# Regulators.net
KiCad netlist of a schematic drawn in Altium Designer
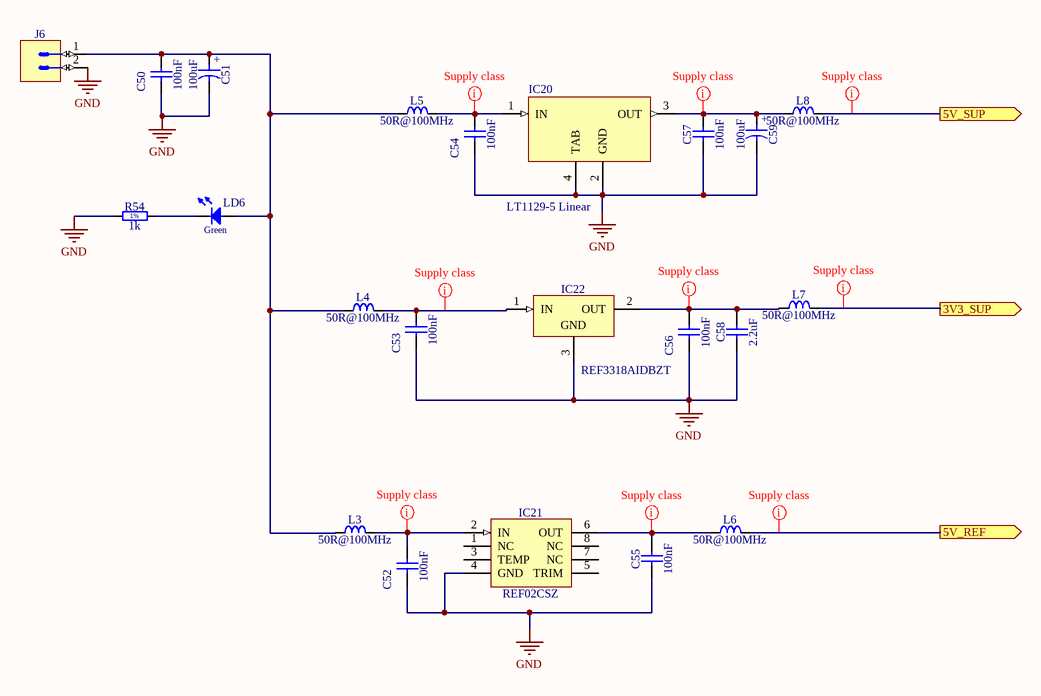
[diagram p0: Regulators.SchDoc]

(export (version "E")
  (design (tool "Eeschema 10.0.6"))
  (components
    (comp (ref "C50")
      (value "100nF")
      (footprint "CAPC2012X135N")
      (description "Non-polarised capacitor")
      (fields
        (field (name "PART NUMBER") "CC0805_100NF_50V_10%_X7R")
        (field (name "VOLTAGE") "50V")
        (field (name "AUTHOR") "CERN DEM JLC")
      )
      (libsource (lib "Capacitors") (part "Capacitor - non polarized"))
    )
    (comp (ref "C51")
      (value "100uF")
      (footprint "CAPAE660X540N")
      (description "Polarised capacitor")
      (fields
        (field (name "PART NUMBER") "CAE660-540_100UF_16V_20%")
        (field (name "VOLTAGE") "16V")
        (field (name "AUTHOR") "CERN DEM JLC")
      )
      (libsource (lib "Capacitors") (part "Capacitor - polarized"))
    )
    (comp (ref "C52")
      (value "100nF")
      (footprint "CAPC2012X135N")
      (description "Non-polarised capacitor")
      (fields
        (field (name "PART NUMBER") "CC0805_100NF_50V_10%_X7R")
        (field (name "VOLTAGE") "50V")
        (field (name "AUTHOR") "CERN DEM JLC")
      )
      (libsource (lib "Capacitors") (part "Capacitor - non polarized"))
    )
    (comp (ref "C53")
      (value "100nF")
      (footprint "CAPC2012X135N")
      (description "Non-polarised capacitor")
      (fields
        (field (name "PART NUMBER") "CC0805_100NF_50V_10%_X7R")
        (field (name "VOLTAGE") "50V")
        (field (name "AUTHOR") "CERN DEM JLC")
      )
      (libsource (lib "Capacitors") (part "Capacitor - non polarized"))
    )
    (comp (ref "C54")
      (value "100nF")
      (footprint "CAPC2012X135N")
      (description "Non-polarised capacitor")
      (fields
        (field (name "PART NUMBER") "CC0805_100NF_50V_10%_X7R")
        (field (name "VOLTAGE") "50V")
        (field (name "AUTHOR") "CERN DEM JLC")
      )
      (libsource (lib "Capacitors") (part "Capacitor - non polarized"))
    )
    (comp (ref "C55")
      (value "100nF")
      (footprint "CAPC2012X135N")
      (description "Non-polarised capacitor")
      (fields
        (field (name "PART NUMBER") "CC0805_100NF_50V_10%_X7R")
        (field (name "VOLTAGE") "50V")
        (field (name "AUTHOR") "CERN DEM JLC")
      )
      (libsource (lib "Capacitors") (part "Capacitor - non polarized"))
    )
    (comp (ref "C56")
      (value "100nF")
      (footprint "CAPC2012X135N")
      (description "Non-polarised capacitor")
      (fields
        (field (name "PART NUMBER") "CC0805_100NF_50V_10%_X7R")
        (field (name "VOLTAGE") "50V")
        (field (name "AUTHOR") "CERN DEM JLC")
      )
      (libsource (lib "Capacitors") (part "Capacitor - non polarized"))
    )
    (comp (ref "C57")
      (value "100nF")
      (footprint "CAPC2012X135N")
      (description "Non-polarised capacitor")
      (fields
        (field (name "PART NUMBER") "CC0805_100NF_50V_10%_X7R")
        (field (name "VOLTAGE") "50V")
        (field (name "AUTHOR") "CERN DEM JLC")
      )
      (libsource (lib "Capacitors") (part "Capacitor - non polarized"))
    )
    (comp (ref "C58")
      (value "2.2uF")
      (footprint "CAPC2012X135N")
      (description "Non-polarised capacitor")
      (fields
        (field (name "PART NUMBER") "CC0805_2.2UF_16V_10%_X7R")
        (field (name "VOLTAGE") "16V")
        (field (name "AUTHOR") "CERN DEM JLC")
      )
      (libsource (lib "Capacitors") (part "Capacitor - non polarized"))
    )
    (comp (ref "C59")
      (value "100uF")
      (footprint "CAPAE660X540N")
      (description "Polarised capacitor")
      (fields
        (field (name "PART NUMBER") "CAE660-540_100UF_16V_20%")
        (field (name "VOLTAGE") "16V")
        (field (name "AUTHOR") "CERN DEM JLC")
      )
      (libsource (lib "Capacitors") (part "Capacitor - polarized"))
    )
    (comp (ref "IC20")
      (value "LT1129-5 Linear")
      (footprint "SOT230P700X175-4N")
      (fields (field (name "MANUFACTURER") "Linear"))
      (libsource (lib "Additional") (part "LT1129-5"))
    )
    (comp (ref "IC21")
      (value "REF02CSZ")
      (footprint "SOIC127P600X175-8N")
      (description "Precision Voltage Reference/Temperature Transducer")
      (fields (field (name "MANUFACTURER") "ANALOG DEVICES") (field (name "AUTHOR") "CERN DEM JLC"))
      (libsource (lib "ICs And Semiconductors") (part "REF02CSZ"))
    )
    (comp (ref "IC22")
      (value "REF3318AIDBZT")
      (footprint "SOT95P237X112-3N")
      (description "3-Terminal Regulator 1=IN 2=OUT 3=GND")
      (fields (field (name "MANUFACTURER") "TEXAS INSTRUMENTS") (field (name "AUTHOR") "CERN DEM JLC"))
      (libsource (lib "ICs And Semiconductors") (part "REG3 1IN-2OUT-3GND"))
    )
    (comp (ref "J6")
      (value "MATE-N-LOK")
      (footprint "TYCO_350786-1")
      (description "Connector 2 Male")
      (fields
        (field (name "PART NUMBER") "TYCO_350786-1")
        (field (name "MANUFACTURER") "TYCO ELECTRONICS")
        (field (name "AUTHOR") "CERN DEM JMW")
      )
      (libsource (lib "Connectors") (part "Connector 2 Male"))
    )
    (comp (ref "L3")
      (value "50R@100MHz")
      (footprint "IND_MURATA_BLM31PG")
      (description "Inductor")
      (fields
        (field (name "PART NUMBER") "IND1206_MURATA_BLM31PG500SN1")
        (field (name "POWER") "3.5A")
        (field (name "AUTHOR") "CERN DEM JLC")
      )
      (libsource (lib "Inductors & Transformers") (part "Inductor"))
    )
    (comp (ref "L4")
      (value "50R@100MHz")
      (footprint "IND_MURATA_BLM31PG")
      (description "Inductor")
      (fields
        (field (name "PART NUMBER") "IND1206_MURATA_BLM31PG500SN1")
        (field (name "POWER") "3.5A")
        (field (name "AUTHOR") "CERN DEM JLC")
      )
      (libsource (lib "Inductors & Transformers") (part "Inductor"))
    )
    (comp (ref "L5")
      (value "50R@100MHz")
      (footprint "IND_MURATA_BLM31PG")
      (description "Inductor")
      (fields
        (field (name "PART NUMBER") "IND1206_MURATA_BLM31PG500SN1")
        (field (name "POWER") "3.5A")
        (field (name "AUTHOR") "CERN DEM JLC")
      )
      (libsource (lib "Inductors & Transformers") (part "Inductor"))
    )
    (comp (ref "L6")
      (value "50R@100MHz")
      (footprint "IND_MURATA_BLM31PG")
      (description "Inductor")
      (fields
        (field (name "PART NUMBER") "IND1206_MURATA_BLM31PG500SN1")
        (field (name "POWER") "3.5A")
        (field (name "AUTHOR") "CERN DEM JLC")
      )
      (libsource (lib "Inductors & Transformers") (part "Inductor"))
    )
    (comp (ref "L7")
      (value "50R@100MHz")
      (footprint "IND_MURATA_BLM31PG")
      (description "Inductor")
      (fields
        (field (name "PART NUMBER") "IND1206_MURATA_BLM31PG500SN1")
        (field (name "POWER") "3.5A")
        (field (name "AUTHOR") "CERN DEM JLC")
      )
      (libsource (lib "Inductors & Transformers") (part "Inductor"))
    )
    (comp (ref "L8")
      (value "50R@100MHz")
      (footprint "IND_MURATA_BLM31PG")
      (description "Inductor")
      (fields
        (field (name "PART NUMBER") "IND1206_MURATA_BLM31PG500SN1")
        (field (name "POWER") "3.5A")
        (field (name "AUTHOR") "CERN DEM JLC")
      )
      (libsource (lib "Inductors & Transformers") (part "Inductor"))
    )
    (comp (ref "LD6")
      (value "Green")
      (footprint "LED_OSRAM_LGR971")
      (description "LED Green 1C 2A")
      (fields
        (field (name "PART NUMBER") "LED_OSRAM_LGR971")
        (field (name "MANUFACTURER") "OSRAM")
        (field (name "AUTHOR") "CERN DEM JLC")
      )
      (libsource (lib "ICs And Semiconductors") (part "LED Green 1C 2A"))
    )
    (comp (ref "R54")
      (value "1k")
      (footprint "RESC2012X60N")
      (description "Resistor - 1%")
      (fields
        (field (name "PART NUMBER") "R0805_1K_1%_0.125W_100PPM")
        (field (name "POWER") "0.125W")
        (field (name "AUTHOR") "CERN DEM JLC")
      )
      (libsource (lib "Resistors") (part "Resistor - 1%"))
    )
  )
  (nets
    (net (code "1") (name "/3V3_SUP") (class "Default")
      (node (ref "L7") (pin "2") (pinfunction "2_2") (pintype "passive"))
    )
    (net (code "2") (name "/5V_REF") (class "Default")
      (node (ref "L6") (pin "2") (pinfunction "2_2") (pintype "passive"))
    )
    (net (code "3") (name "/5V_SUP") (class "Default")
      (node (ref "L8") (pin "2") (pinfunction "2_2") (pintype "passive"))
    )
    (net (code "4") (name "GND") (class "Default")
      (node (ref "C50") (pin "1") (pinfunction "1_1") (pintype "passive"))
      (node (ref "C51") (pin "2") (pinfunction "2_2") (pintype "passive"))
      (node (ref "C52") (pin "1") (pinfunction "1_1") (pintype "passive"))
      (node (ref "C53") (pin "1") (pinfunction "1_1") (pintype "passive"))
      (node (ref "C54") (pin "1") (pinfunction "1_1") (pintype "passive"))
      (node (ref "C55") (pin "1") (pinfunction "1_1") (pintype "passive"))
      (node (ref "C56") (pin "1") (pinfunction "1_1") (pintype "passive"))
      (node (ref "C57") (pin "1") (pinfunction "1_1") (pintype "passive"))
      (node (ref "C58") (pin "1") (pinfunction "1_1") (pintype "passive"))
      (node (ref "C59") (pin "2") (pinfunction "2_2") (pintype "passive"))
      (node (ref "IC20") (pin "2") (pinfunction "GND_2") (pintype "power_in"))
      (node (ref "IC20") (pin "4") (pinfunction "TAB_4") (pintype "power_in"))
      (node (ref "IC21") (pin "4") (pinfunction "GND_4") (pintype "power_in"))
      (node (ref "IC22") (pin "3") (pinfunction "GND_3") (pintype "power_in"))
      (node (ref "J6") (pin "2") (pinfunction "2_2") (pintype "bidirectional"))
      (node (ref "R54") (pin "1") (pinfunction "1_1") (pintype "passive"))
    )
    (net (code "5") (name "Net-(IC20-IN)") (class "Default")
      (node (ref "C54") (pin "2") (pinfunction "2_2") (pintype "passive"))
      (node (ref "IC20") (pin "1") (pinfunction "IN_1") (pintype "input"))
      (node (ref "L5") (pin "2") (pinfunction "2_2") (pintype "passive"))
    )
    (net (code "6") (name "Net-(IC20-OUT)") (class "Default")
      (node (ref "C57") (pin "2") (pinfunction "2_2") (pintype "passive"))
      (node (ref "C59") (pin "1") (pinfunction "1_1") (pintype "passive"))
      (node (ref "IC20") (pin "3") (pinfunction "OUT_3") (pintype "output"))
      (node (ref "L8") (pin "1") (pinfunction "1_1") (pintype "passive"))
    )
    (net (code "7") (name "Net-(IC21-IN)") (class "Default")
      (node (ref "C52") (pin "2") (pinfunction "2_2") (pintype "passive"))
      (node (ref "IC21") (pin "2") (pinfunction "IN_2") (pintype "input"))
      (node (ref "L3") (pin "2") (pinfunction "2_2") (pintype "passive"))
    )
    (net (code "8") (name "Net-(IC21-OUT)") (class "Default")
      (node (ref "C55") (pin "2") (pinfunction "2_2") (pintype "passive"))
      (node (ref "IC21") (pin "6") (pinfunction "OUT_6") (pintype "power_in"))
      (node (ref "L6") (pin "1") (pinfunction "1_1") (pintype "passive"))
    )
    (net (code "9") (name "Net-(IC22-IN)") (class "Default")
      (node (ref "C53") (pin "2") (pinfunction "2_2") (pintype "passive"))
      (node (ref "IC22") (pin "1") (pinfunction "IN_1") (pintype "input"))
      (node (ref "L4") (pin "2") (pinfunction "2_2") (pintype "passive"))
    )
    (net (code "10") (name "Net-(IC22-OUT)") (class "Default")
      (node (ref "C56") (pin "2") (pinfunction "2_2") (pintype "passive"))
      (node (ref "C58") (pin "2") (pinfunction "2_2") (pintype "passive"))
      (node (ref "IC22") (pin "2") (pinfunction "OUT_2") (pintype "power_in"))
      (node (ref "L7") (pin "1") (pinfunction "1_1") (pintype "passive"))
    )
    (net (code "11") (name "Net-(LD6-A)") (class "Default")
      (node (ref "C50") (pin "2") (pinfunction "2_2") (pintype "passive"))
      (node (ref "C51") (pin "1") (pinfunction "1_1") (pintype "passive"))
      (node (ref "J6") (pin "1") (pinfunction "1_1") (pintype "bidirectional"))
      (node (ref "L3") (pin "1") (pinfunction "1_1") (pintype "passive"))
      (node (ref "L4") (pin "1") (pinfunction "1_1") (pintype "passive"))
      (node (ref "L5") (pin "1") (pinfunction "1_1") (pintype "passive"))
      (node (ref "LD6") (pin "2") (pinfunction "A_2") (pintype "passive"))
    )
    (net (code "12") (name "Net-(LD6-C)") (class "Default")
      (node (ref "LD6") (pin "1") (pinfunction "C_1") (pintype "passive"))
      (node (ref "R54") (pin "2") (pinfunction "2_2") (pintype "passive"))
    )
    (net (code "13") (name "unconnected-(IC21-NC-Pad1)") (class "Default")
      (node (ref "IC21") (pin "1") (pinfunction "NC_1") (pintype "passive"))
    )
    (net (code "14") (name "unconnected-(IC21-NC-Pad7)") (class "Default")
      (node (ref "IC21") (pin "7") (pinfunction "NC_7") (pintype "passive"))
    )
    (net (code "15") (name "unconnected-(IC21-NC-Pad8)") (class "Default")
      (node (ref "IC21") (pin "8") (pinfunction "NC_8") (pintype "passive"))
    )
    (net (code "16") (name "unconnected-(IC21-TEMP-Pad3)") (class "Default")
      (node (ref "IC21") (pin "3") (pinfunction "TEMP_3") (pintype "passive"))
    )
    (net (code "17") (name "unconnected-(IC21-TRIM-Pad5)") (class "Default")
      (node (ref "IC21") (pin "5") (pinfunction "TRIM_5") (pintype "passive"))
    )
  )
)
